# stirrer_power_dpak.net
KiCad netlist of a schematic drawn in EAGLE
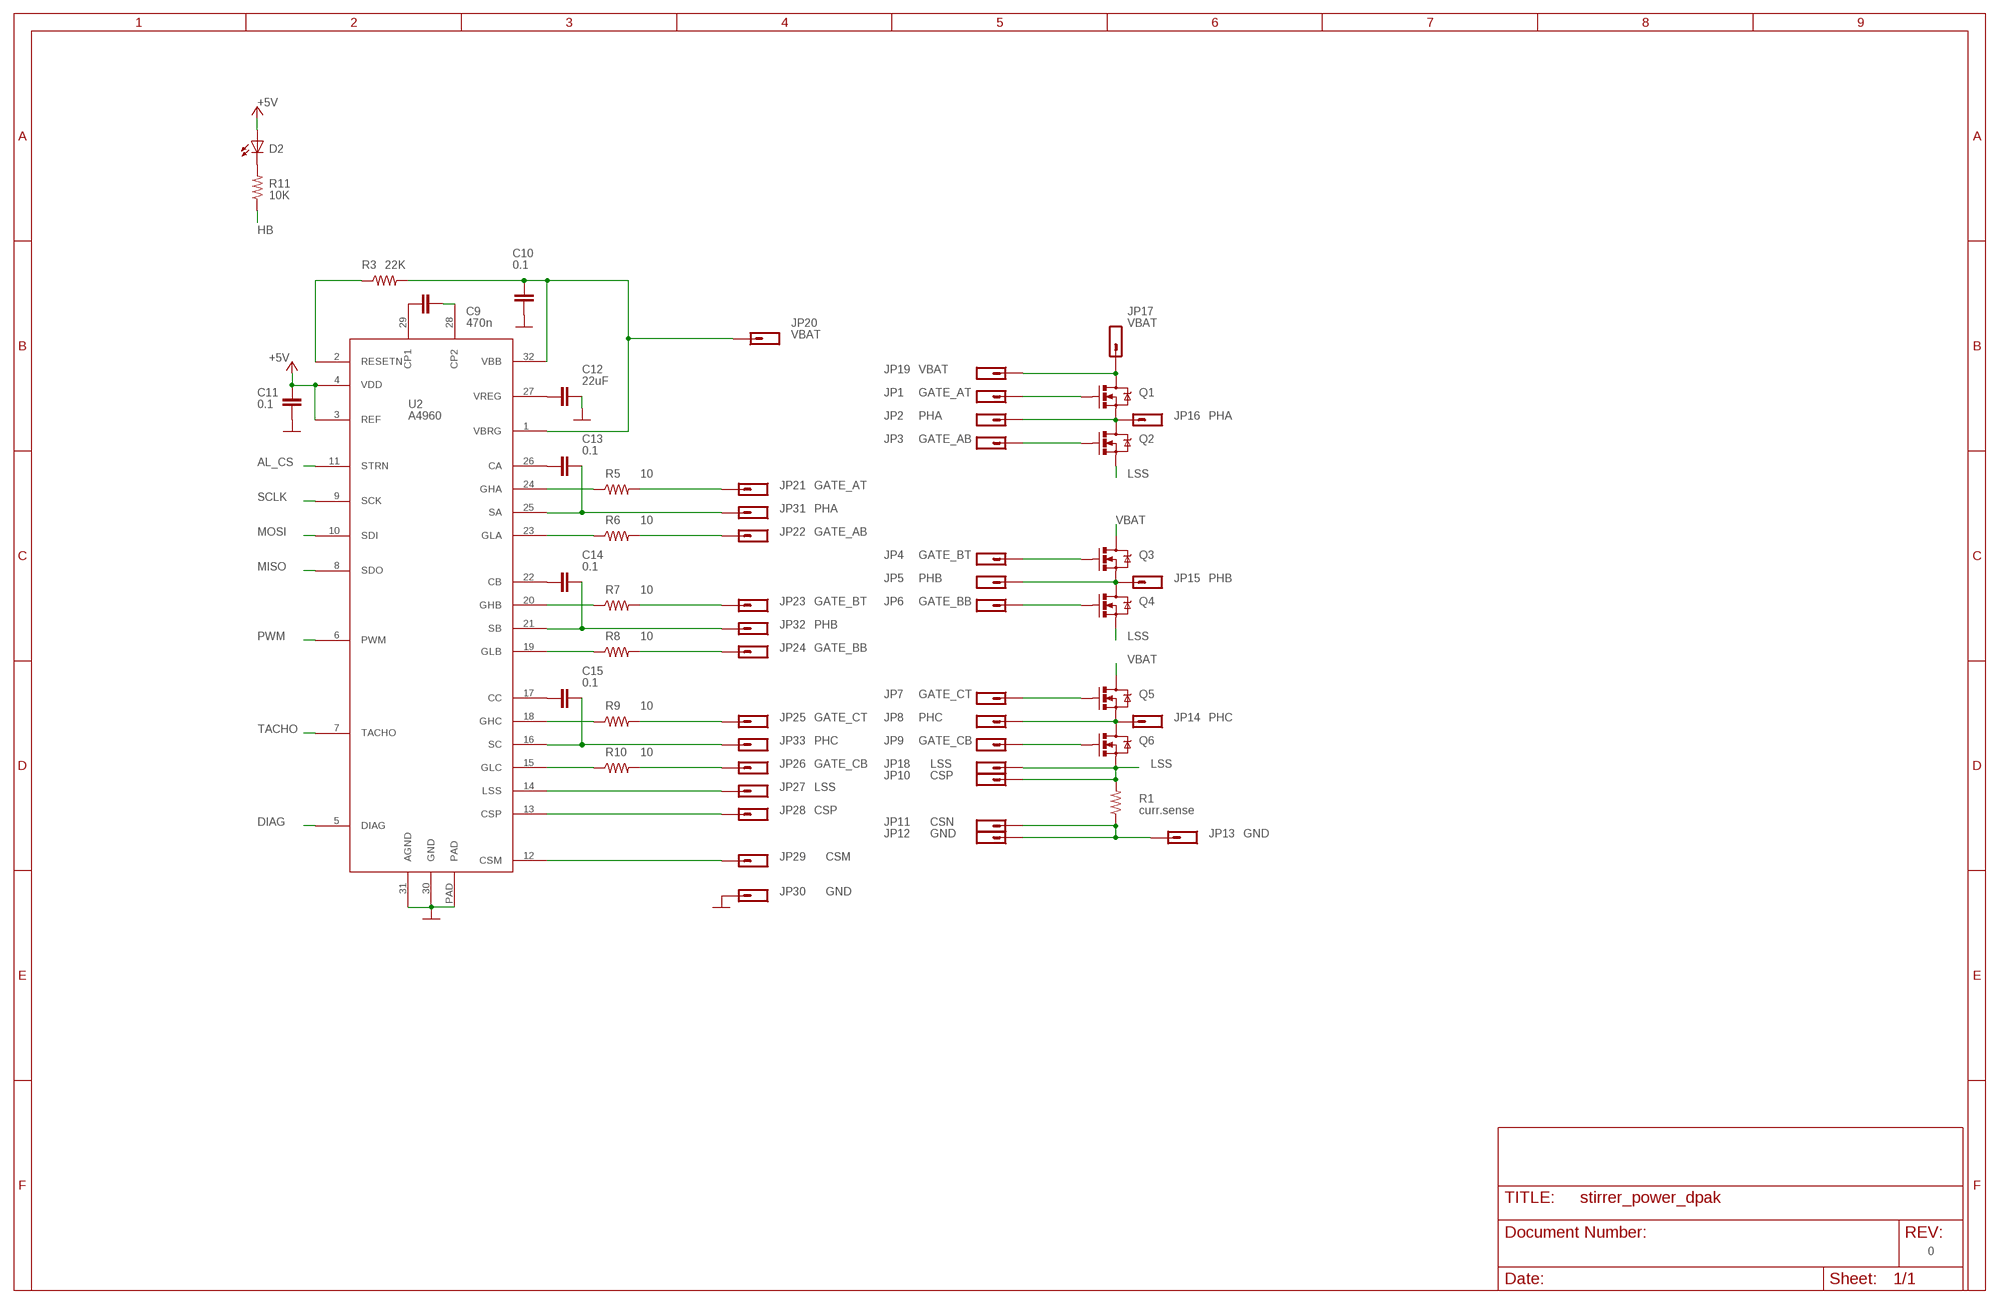
[diagram p0: schematic, sheet 1]

(export (version "E")
  (design (tool "Eeschema 10.0.6"))
  (components
    (comp (ref "C9")
      (value "470n")
      (footprint "eagle-import:0603")
      (libsource (lib "eagle-import") (part "C-0603"))
    )
    (comp (ref "C10")
      (value "0.1")
      (footprint "eagle-import:0603")
      (libsource (lib "eagle-import") (part "C-0603"))
    )
    (comp (ref "C11")
      (value "0.1")
      (footprint "eagle-import:0603")
      (libsource (lib "eagle-import") (part "C-0603"))
    )
    (comp (ref "C12")
      (value "22uF")
      (footprint "eagle-import:1206")
      (libsource (lib "eagle-import") (part "CAP1206"))
    )
    (comp (ref "C13")
      (value "0.1")
      (footprint "eagle-import:0603")
      (libsource (lib "eagle-import") (part "C-0603"))
    )
    (comp (ref "C14")
      (value "0.1")
      (footprint "eagle-import:0603")
      (libsource (lib "eagle-import") (part "C-0603"))
    )
    (comp (ref "C15")
      (value "0.1")
      (footprint "eagle-import:0603")
      (libsource (lib "eagle-import") (part "C-0603"))
    )
    (comp (ref "D2")
      (value "LED5MM")
      (footprint "eagle-import:LED5MM")
      (libsource (lib "eagle-import") (part "LED5MM"))
    )
    (comp (ref "JP1")
      (value "GATE_AT")
      (footprint "eagle-import:1X01_TT")
      (libsource (lib "eagle-import") (part "M01-TT"))
    )
    (comp (ref "JP2")
      (value "PHA")
      (footprint "eagle-import:1X01_TT")
      (libsource (lib "eagle-import") (part "M01-TT"))
    )
    (comp (ref "JP3")
      (value "GATE_AB")
      (footprint "eagle-import:1X01_TT")
      (libsource (lib "eagle-import") (part "M01-TT"))
    )
    (comp (ref "JP4")
      (value "GATE_BT")
      (footprint "eagle-import:1X01_TT")
      (libsource (lib "eagle-import") (part "M01-TT"))
    )
    (comp (ref "JP5")
      (value "PHB")
      (footprint "eagle-import:1X01_TT")
      (libsource (lib "eagle-import") (part "M01-TT"))
    )
    (comp (ref "JP6")
      (value "GATE_BB")
      (footprint "eagle-import:1X01_TT")
      (libsource (lib "eagle-import") (part "M01-TT"))
    )
    (comp (ref "JP7")
      (value "GATE_CT")
      (footprint "eagle-import:1X01_TT")
      (libsource (lib "eagle-import") (part "M01-TT"))
    )
    (comp (ref "JP8")
      (value "PHC")
      (footprint "eagle-import:1X01_TT")
      (libsource (lib "eagle-import") (part "M01-TT"))
    )
    (comp (ref "JP9")
      (value "GATE_CB")
      (footprint "eagle-import:1X01_TT")
      (libsource (lib "eagle-import") (part "M01-TT"))
    )
    (comp (ref "JP10")
      (value "CSP")
      (footprint "eagle-import:1X01_TT")
      (libsource (lib "eagle-import") (part "M01-TT"))
    )
    (comp (ref "JP11")
      (value "CSN")
      (footprint "eagle-import:1X01_TT")
      (libsource (lib "eagle-import") (part "M01-TT"))
    )
    (comp (ref "JP12")
      (value "GND")
      (footprint "eagle-import:1X01_TT")
      (libsource (lib "eagle-import") (part "M01-TT"))
    )
    (comp (ref "JP13")
      (value "GND")
      (footprint "eagle-import:1X01_TT")
      (libsource (lib "eagle-import") (part "M01-TT"))
    )
    (comp (ref "JP14")
      (value "PHC")
      (footprint "eagle-import:1X01_TT")
      (libsource (lib "eagle-import") (part "M01-TT"))
    )
    (comp (ref "JP15")
      (value "PHB")
      (footprint "eagle-import:1X01_TT")
      (libsource (lib "eagle-import") (part "M01-TT"))
    )
    (comp (ref "JP16")
      (value "PHA")
      (footprint "eagle-import:1X01_TT")
      (libsource (lib "eagle-import") (part "M01-TT"))
    )
    (comp (ref "JP17")
      (value "VBAT")
      (footprint "eagle-import:1X01_TT")
      (libsource (lib "eagle-import") (part "M01-TT"))
    )
    (comp (ref "JP18")
      (value "LSS")
      (footprint "eagle-import:1X01_TT")
      (libsource (lib "eagle-import") (part "M01-TT"))
    )
    (comp (ref "JP19")
      (value "VBAT")
      (footprint "eagle-import:1X01_TT")
      (libsource (lib "eagle-import") (part "M01-TT"))
    )
    (comp (ref "JP20")
      (value "VBAT")
      (footprint "eagle-import:1X01_TT")
      (libsource (lib "eagle-import") (part "M01-TT"))
    )
    (comp (ref "JP21")
      (value "GATE_AT")
      (footprint "eagle-import:1X01_TT")
      (libsource (lib "eagle-import") (part "M01-TT"))
    )
    (comp (ref "JP22")
      (value "GATE_AB")
      (footprint "eagle-import:1X01_TT")
      (libsource (lib "eagle-import") (part "M01-TT"))
    )
    (comp (ref "JP23")
      (value "GATE_BT")
      (footprint "eagle-import:1X01_TT")
      (libsource (lib "eagle-import") (part "M01-TT"))
    )
    (comp (ref "JP24")
      (value "GATE_BB")
      (footprint "eagle-import:1X01_TT")
      (libsource (lib "eagle-import") (part "M01-TT"))
    )
    (comp (ref "JP25")
      (value "GATE_CT")
      (footprint "eagle-import:1X01_TT")
      (libsource (lib "eagle-import") (part "M01-TT"))
    )
    (comp (ref "JP26")
      (value "GATE_CB")
      (footprint "eagle-import:1X01_TT")
      (libsource (lib "eagle-import") (part "M01-TT"))
    )
    (comp (ref "JP27")
      (value "LSS")
      (footprint "eagle-import:1X01_TT")
      (libsource (lib "eagle-import") (part "M01-TT"))
    )
    (comp (ref "JP28")
      (value "CSP")
      (footprint "eagle-import:1X01_TT")
      (libsource (lib "eagle-import") (part "M01-TT"))
    )
    (comp (ref "JP29")
      (value "CSM")
      (footprint "eagle-import:1X01_TT")
      (libsource (lib "eagle-import") (part "M01-TT"))
    )
    (comp (ref "JP30")
      (value "GND")
      (footprint "eagle-import:1X01_TT")
      (libsource (lib "eagle-import") (part "M01-TT"))
    )
    (comp (ref "JP31")
      (value "PHA")
      (footprint "eagle-import:1X01_TT")
      (libsource (lib "eagle-import") (part "M01-TT"))
    )
    (comp (ref "JP32")
      (value "PHB")
      (footprint "eagle-import:1X01_TT")
      (libsource (lib "eagle-import") (part "M01-TT"))
    )
    (comp (ref "JP33")
      (value "PHC")
      (footprint "eagle-import:1X01_TT")
      (libsource (lib "eagle-import") (part "M01-TT"))
    )
    (comp (ref "Q1")
      (value "MOSFET-NCHANNEL-DPAK")
      (footprint "eagle-import:DPAK")
      (libsource (lib "eagle-import") (part "MOSFET-NCHANNEL-DPAK"))
    )
    (comp (ref "Q2")
      (value "MOSFET-NCHANNEL-DPAK")
      (footprint "eagle-import:DPAK")
      (libsource (lib "eagle-import") (part "MOSFET-NCHANNEL-DPAK"))
    )
    (comp (ref "Q3")
      (value "MOSFET-NCHANNEL-DPAK")
      (footprint "eagle-import:DPAK")
      (libsource (lib "eagle-import") (part "MOSFET-NCHANNEL-DPAK"))
    )
    (comp (ref "Q4")
      (value "MOSFET-NCHANNEL-DPAK")
      (footprint "eagle-import:DPAK")
      (libsource (lib "eagle-import") (part "MOSFET-NCHANNEL-DPAK"))
    )
    (comp (ref "Q5")
      (value "MOSFET-NCHANNEL-DPAK")
      (footprint "eagle-import:DPAK")
      (libsource (lib "eagle-import") (part "MOSFET-NCHANNEL-DPAK"))
    )
    (comp (ref "Q6")
      (value "MOSFET-NCHANNEL-DPAK")
      (footprint "eagle-import:DPAK")
      (libsource (lib "eagle-import") (part "MOSFET-NCHANNEL-DPAK"))
    )
    (comp (ref "R1")
      (value "curr.sense")
      (footprint "eagle-import:2512")
      (libsource (lib "eagle-import") (part "RESISTOR-2512"))
    )
    (comp (ref "R3")
      (value "22K")
      (footprint "eagle-import:0603")
      (libsource (lib "eagle-import") (part "RESISTOR-0603"))
    )
    (comp (ref "R5")
      (value "10")
      (footprint "eagle-import:0603")
      (libsource (lib "eagle-import") (part "RESISTOR-0603"))
    )
    (comp (ref "R6")
      (value "10")
      (footprint "eagle-import:0603")
      (libsource (lib "eagle-import") (part "RESISTOR-0603"))
    )
    (comp (ref "R7")
      (value "10")
      (footprint "eagle-import:0603")
      (libsource (lib "eagle-import") (part "RESISTOR-0603"))
    )
    (comp (ref "R8")
      (value "10")
      (footprint "eagle-import:0603")
      (libsource (lib "eagle-import") (part "RESISTOR-0603"))
    )
    (comp (ref "R9")
      (value "10")
      (footprint "eagle-import:0603")
      (libsource (lib "eagle-import") (part "RESISTOR-0603"))
    )
    (comp (ref "R10")
      (value "10")
      (footprint "eagle-import:0603")
      (libsource (lib "eagle-import") (part "RESISTOR-0603"))
    )
    (comp (ref "R11")
      (value "10K")
      (footprint "eagle-import:0603")
      (libsource (lib "eagle-import") (part "RESISTOR-0603"))
    )
    (comp (ref "U2")
      (value "A4960")
      (footprint "eagle-import:LQPF-32")
      (libsource (lib "eagle-import") (part "A4960"))
    )
  )
  (nets
    (net (code "1") (name "+5V") (class "Default")
      (node (ref "C11") (pin "2") (pinfunction "2_2") (pintype "passive"))
      (node (ref "D2") (pin "A") (pinfunction "A_A") (pintype "passive"))
      (node (ref "U2") (pin "3") (pinfunction "REF_3") (pintype "bidirectional"))
      (node (ref "U2") (pin "4") (pinfunction "VDD_4") (pintype "bidirectional"))
    )
    (net (code "2") (name "/AL_CS") (class "Default")
      (node (ref "U2") (pin "11") (pinfunction "STRN_11") (pintype "bidirectional"))
    )
    (net (code "3") (name "/DIAG") (class "Default")
      (node (ref "U2") (pin "5") (pinfunction "DIAG_5") (pintype "bidirectional"))
    )
    (net (code "4") (name "/HB") (class "Default")
      (node (ref "R11") (pin "1") (pinfunction "1_1") (pintype "passive"))
    )
    (net (code "5") (name "/LSS") (class "Default")
      (node (ref "JP10") (pin "1") (pinfunction "1_1") (pintype "passive"))
      (node (ref "JP18") (pin "1") (pinfunction "1_1") (pintype "passive"))
      (node (ref "Q2") (pin "3") (pinfunction "S_3") (pintype "passive"))
      (node (ref "Q4") (pin "3") (pinfunction "S_3") (pintype "passive"))
      (node (ref "Q6") (pin "3") (pinfunction "S_3") (pintype "passive"))
      (node (ref "R1") (pin "P$2") (pinfunction "2_P$2") (pintype "passive"))
    )
    (net (code "6") (name "/MISO") (class "Default")
      (node (ref "U2") (pin "8") (pinfunction "SDO_8") (pintype "bidirectional"))
    )
    (net (code "7") (name "/MOSI") (class "Default")
      (node (ref "U2") (pin "10") (pinfunction "SDI_10") (pintype "bidirectional"))
    )
    (net (code "8") (name "/PWM") (class "Default")
      (node (ref "U2") (pin "6") (pinfunction "PWM_6") (pintype "bidirectional"))
    )
    (net (code "9") (name "/SCLK") (class "Default")
      (node (ref "U2") (pin "9") (pinfunction "SCK_9") (pintype "bidirectional"))
    )
    (net (code "10") (name "/TACHO") (class "Default")
      (node (ref "U2") (pin "7") (pinfunction "TACHO_7") (pintype "bidirectional"))
    )
    (net (code "11") (name "/VBAT") (class "Default")
      (node (ref "JP17") (pin "1") (pinfunction "1_1") (pintype "passive"))
      (node (ref "JP19") (pin "1") (pinfunction "1_1") (pintype "passive"))
      (node (ref "Q1") (pin "4") (pinfunction "D_4") (pintype "passive"))
      (node (ref "Q3") (pin "4") (pinfunction "D_4") (pintype "passive"))
      (node (ref "Q5") (pin "4") (pinfunction "D_4") (pintype "passive"))
    )
    (net (code "12") (name "GND") (class "Default")
      (node (ref "C10") (pin "1") (pinfunction "1_1") (pintype "passive"))
      (node (ref "C11") (pin "1") (pinfunction "1_1") (pintype "passive"))
      (node (ref "C12") (pin "2") (pinfunction "2_2") (pintype "passive"))
      (node (ref "JP11") (pin "1") (pinfunction "1_1") (pintype "passive"))
      (node (ref "JP12") (pin "1") (pinfunction "1_1") (pintype "passive"))
      (node (ref "JP13") (pin "1") (pinfunction "1_1") (pintype "passive"))
      (node (ref "JP30") (pin "1") (pinfunction "1_1") (pintype "passive"))
      (node (ref "R1") (pin "P$1") (pinfunction "1_P$1") (pintype "passive"))
      (node (ref "U2") (pin "30") (pinfunction "GND_30") (pintype "bidirectional"))
      (node (ref "U2") (pin "31") (pinfunction "AGND_31") (pintype "bidirectional"))
      (node (ref "U2") (pin "PAD") (pinfunction "PAD_PAD") (pintype "bidirectional"))
    )
    (net (code "13") (name "Net-(D2-C)") (class "Default")
      (node (ref "D2") (pin "K") (pinfunction "C_K") (pintype "passive"))
      (node (ref "R11") (pin "2") (pinfunction "2_2") (pintype "passive"))
    )
    (net (code "14") (name "Net-(JP21-Pad1)") (class "Default")
      (node (ref "JP21") (pin "1") (pinfunction "1_1") (pintype "passive"))
      (node (ref "R5") (pin "2") (pinfunction "2_2") (pintype "passive"))
    )
    (net (code "15") (name "Net-(JP22-Pad1)") (class "Default")
      (node (ref "JP22") (pin "1") (pinfunction "1_1") (pintype "passive"))
      (node (ref "R6") (pin "2") (pinfunction "2_2") (pintype "passive"))
    )
    (net (code "16") (name "Net-(JP23-Pad1)") (class "Default")
      (node (ref "JP23") (pin "1") (pinfunction "1_1") (pintype "passive"))
      (node (ref "R7") (pin "2") (pinfunction "2_2") (pintype "passive"))
    )
    (net (code "17") (name "Net-(JP24-Pad1)") (class "Default")
      (node (ref "JP24") (pin "1") (pinfunction "1_1") (pintype "passive"))
      (node (ref "R8") (pin "2") (pinfunction "2_2") (pintype "passive"))
    )
    (net (code "18") (name "Net-(JP25-Pad1)") (class "Default")
      (node (ref "JP25") (pin "1") (pinfunction "1_1") (pintype "passive"))
      (node (ref "R9") (pin "2") (pinfunction "2_2") (pintype "passive"))
    )
    (net (code "19") (name "Net-(JP26-Pad1)") (class "Default")
      (node (ref "JP26") (pin "1") (pinfunction "1_1") (pintype "passive"))
      (node (ref "R10") (pin "2") (pinfunction "2_2") (pintype "passive"))
    )
    (net (code "20") (name "Net-(Q1-G)") (class "Default")
      (node (ref "JP1") (pin "1") (pinfunction "1_1") (pintype "passive"))
      (node (ref "Q1") (pin "1") (pinfunction "G_1") (pintype "passive"))
    )
    (net (code "21") (name "Net-(Q1-S)") (class "Default")
      (node (ref "JP16") (pin "1") (pinfunction "1_1") (pintype "passive"))
      (node (ref "JP2") (pin "1") (pinfunction "1_1") (pintype "passive"))
      (node (ref "Q1") (pin "3") (pinfunction "S_3") (pintype "passive"))
      (node (ref "Q2") (pin "4") (pinfunction "D_4") (pintype "passive"))
    )
    (net (code "22") (name "Net-(Q2-G)") (class "Default")
      (node (ref "JP3") (pin "1") (pinfunction "1_1") (pintype "passive"))
      (node (ref "Q2") (pin "1") (pinfunction "G_1") (pintype "passive"))
    )
    (net (code "23") (name "Net-(Q3-G)") (class "Default")
      (node (ref "JP4") (pin "1") (pinfunction "1_1") (pintype "passive"))
      (node (ref "Q3") (pin "1") (pinfunction "G_1") (pintype "passive"))
    )
    (net (code "24") (name "Net-(Q3-S)") (class "Default")
      (node (ref "JP15") (pin "1") (pinfunction "1_1") (pintype "passive"))
      (node (ref "JP5") (pin "1") (pinfunction "1_1") (pintype "passive"))
      (node (ref "Q3") (pin "3") (pinfunction "S_3") (pintype "passive"))
      (node (ref "Q4") (pin "4") (pinfunction "D_4") (pintype "passive"))
    )
    (net (code "25") (name "Net-(Q4-G)") (class "Default")
      (node (ref "JP6") (pin "1") (pinfunction "1_1") (pintype "passive"))
      (node (ref "Q4") (pin "1") (pinfunction "G_1") (pintype "passive"))
    )
    (net (code "26") (name "Net-(Q5-G)") (class "Default")
      (node (ref "JP7") (pin "1") (pinfunction "1_1") (pintype "passive"))
      (node (ref "Q5") (pin "1") (pinfunction "G_1") (pintype "passive"))
    )
    (net (code "27") (name "Net-(Q5-S)") (class "Default")
      (node (ref "JP14") (pin "1") (pinfunction "1_1") (pintype "passive"))
      (node (ref "JP8") (pin "1") (pinfunction "1_1") (pintype "passive"))
      (node (ref "Q5") (pin "3") (pinfunction "S_3") (pintype "passive"))
      (node (ref "Q6") (pin "4") (pinfunction "D_4") (pintype "passive"))
    )
    (net (code "28") (name "Net-(Q6-G)") (class "Default")
      (node (ref "JP9") (pin "1") (pinfunction "1_1") (pintype "passive"))
      (node (ref "Q6") (pin "1") (pinfunction "G_1") (pintype "passive"))
    )
    (net (code "29") (name "Net-(U2-CA)") (class "Default")
      (node (ref "C13") (pin "2") (pinfunction "2_2") (pintype "passive"))
      (node (ref "U2") (pin "26") (pinfunction "CA_26") (pintype "bidirectional"))
    )
    (net (code "30") (name "Net-(U2-CB)") (class "Default")
      (node (ref "C14") (pin "2") (pinfunction "2_2") (pintype "passive"))
      (node (ref "U2") (pin "22") (pinfunction "CB_22") (pintype "bidirectional"))
    )
    (net (code "31") (name "Net-(U2-CC)") (class "Default")
      (node (ref "C15") (pin "2") (pinfunction "2_2") (pintype "passive"))
      (node (ref "U2") (pin "17") (pinfunction "CC_17") (pintype "bidirectional"))
    )
    (net (code "32") (name "Net-(U2-CP1)") (class "Default")
      (node (ref "C9") (pin "1") (pinfunction "1_1") (pintype "passive"))
      (node (ref "U2") (pin "29") (pinfunction "CP1_29") (pintype "bidirectional"))
    )
    (net (code "33") (name "Net-(U2-CP2)") (class "Default")
      (node (ref "C9") (pin "2") (pinfunction "2_2") (pintype "passive"))
      (node (ref "U2") (pin "28") (pinfunction "CP2_28") (pintype "bidirectional"))
    )
    (net (code "34") (name "Net-(U2-CSM)") (class "Default")
      (node (ref "JP29") (pin "1") (pinfunction "1_1") (pintype "passive"))
      (node (ref "U2") (pin "12") (pinfunction "CSM_12") (pintype "bidirectional"))
    )
    (net (code "35") (name "Net-(U2-CSP)") (class "Default")
      (node (ref "JP28") (pin "1") (pinfunction "1_1") (pintype "passive"))
      (node (ref "U2") (pin "13") (pinfunction "CSP_13") (pintype "bidirectional"))
    )
    (net (code "36") (name "Net-(U2-GHA)") (class "Default")
      (node (ref "R5") (pin "1") (pinfunction "1_1") (pintype "passive"))
      (node (ref "U2") (pin "24") (pinfunction "GHA_24") (pintype "bidirectional"))
    )
    (net (code "37") (name "Net-(U2-GHB)") (class "Default")
      (node (ref "R7") (pin "1") (pinfunction "1_1") (pintype "passive"))
      (node (ref "U2") (pin "20") (pinfunction "GHB_20") (pintype "bidirectional"))
    )
    (net (code "38") (name "Net-(U2-GHC)") (class "Default")
      (node (ref "R9") (pin "1") (pinfunction "1_1") (pintype "passive"))
      (node (ref "U2") (pin "18") (pinfunction "GHC_18") (pintype "bidirectional"))
    )
    (net (code "39") (name "Net-(U2-GLA)") (class "Default")
      (node (ref "R6") (pin "1") (pinfunction "1_1") (pintype "passive"))
      (node (ref "U2") (pin "23") (pinfunction "GLA_23") (pintype "bidirectional"))
    )
    (net (code "40") (name "Net-(U2-GLB)") (class "Default")
      (node (ref "R8") (pin "1") (pinfunction "1_1") (pintype "passive"))
      (node (ref "U2") (pin "19") (pinfunction "GLB_19") (pintype "bidirectional"))
    )
    (net (code "41") (name "Net-(U2-GLC)") (class "Default")
      (node (ref "R10") (pin "1") (pinfunction "1_1") (pintype "passive"))
      (node (ref "U2") (pin "15") (pinfunction "GLC_15") (pintype "bidirectional"))
    )
    (net (code "42") (name "Net-(U2-LSS)") (class "Default")
      (node (ref "JP27") (pin "1") (pinfunction "1_1") (pintype "passive"))
      (node (ref "U2") (pin "14") (pinfunction "LSS_14") (pintype "bidirectional"))
    )
    (net (code "43") (name "Net-(U2-RESETN)") (class "Default")
      (node (ref "R3") (pin "1") (pinfunction "1_1") (pintype "passive"))
      (node (ref "U2") (pin "2") (pinfunction "RESETN_2") (pintype "bidirectional"))
    )
    (net (code "44") (name "Net-(U2-SA)") (class "Default")
      (node (ref "C13") (pin "1") (pinfunction "1_1") (pintype "passive"))
      (node (ref "JP31") (pin "1") (pinfunction "1_1") (pintype "passive"))
      (node (ref "U2") (pin "25") (pinfunction "SA_25") (pintype "bidirectional"))
    )
    (net (code "45") (name "Net-(U2-SB)") (class "Default")
      (node (ref "C14") (pin "1") (pinfunction "1_1") (pintype "passive"))
      (node (ref "JP32") (pin "1") (pinfunction "1_1") (pintype "passive"))
      (node (ref "U2") (pin "21") (pinfunction "SB_21") (pintype "bidirectional"))
    )
    (net (code "46") (name "Net-(U2-SC)") (class "Default")
      (node (ref "C15") (pin "1") (pinfunction "1_1") (pintype "passive"))
      (node (ref "JP33") (pin "1") (pinfunction "1_1") (pintype "passive"))
      (node (ref "U2") (pin "16") (pinfunction "SC_16") (pintype "bidirectional"))
    )
    (net (code "47") (name "Net-(U2-VBB)") (class "Default")
      (node (ref "C10") (pin "2") (pinfunction "2_2") (pintype "passive"))
      (node (ref "JP20") (pin "1") (pinfunction "1_1") (pintype "passive"))
      (node (ref "R3") (pin "2") (pinfunction "2_2") (pintype "passive"))
      (node (ref "U2") (pin "1") (pinfunction "VBRG_1") (pintype "bidirectional"))
      (node (ref "U2") (pin "32") (pinfunction "VBB_32") (pintype "bidirectional"))
    )
    (net (code "48") (name "Net-(U2-VREG)") (class "Default")
      (node (ref "C12") (pin "1") (pinfunction "1_1") (pintype "passive"))
      (node (ref "U2") (pin "27") (pinfunction "VREG_27") (pintype "bidirectional"))
    )
  )
)
